# Hi-Hat2.net
KiCad netlist of a schematic drawn in EAGLE
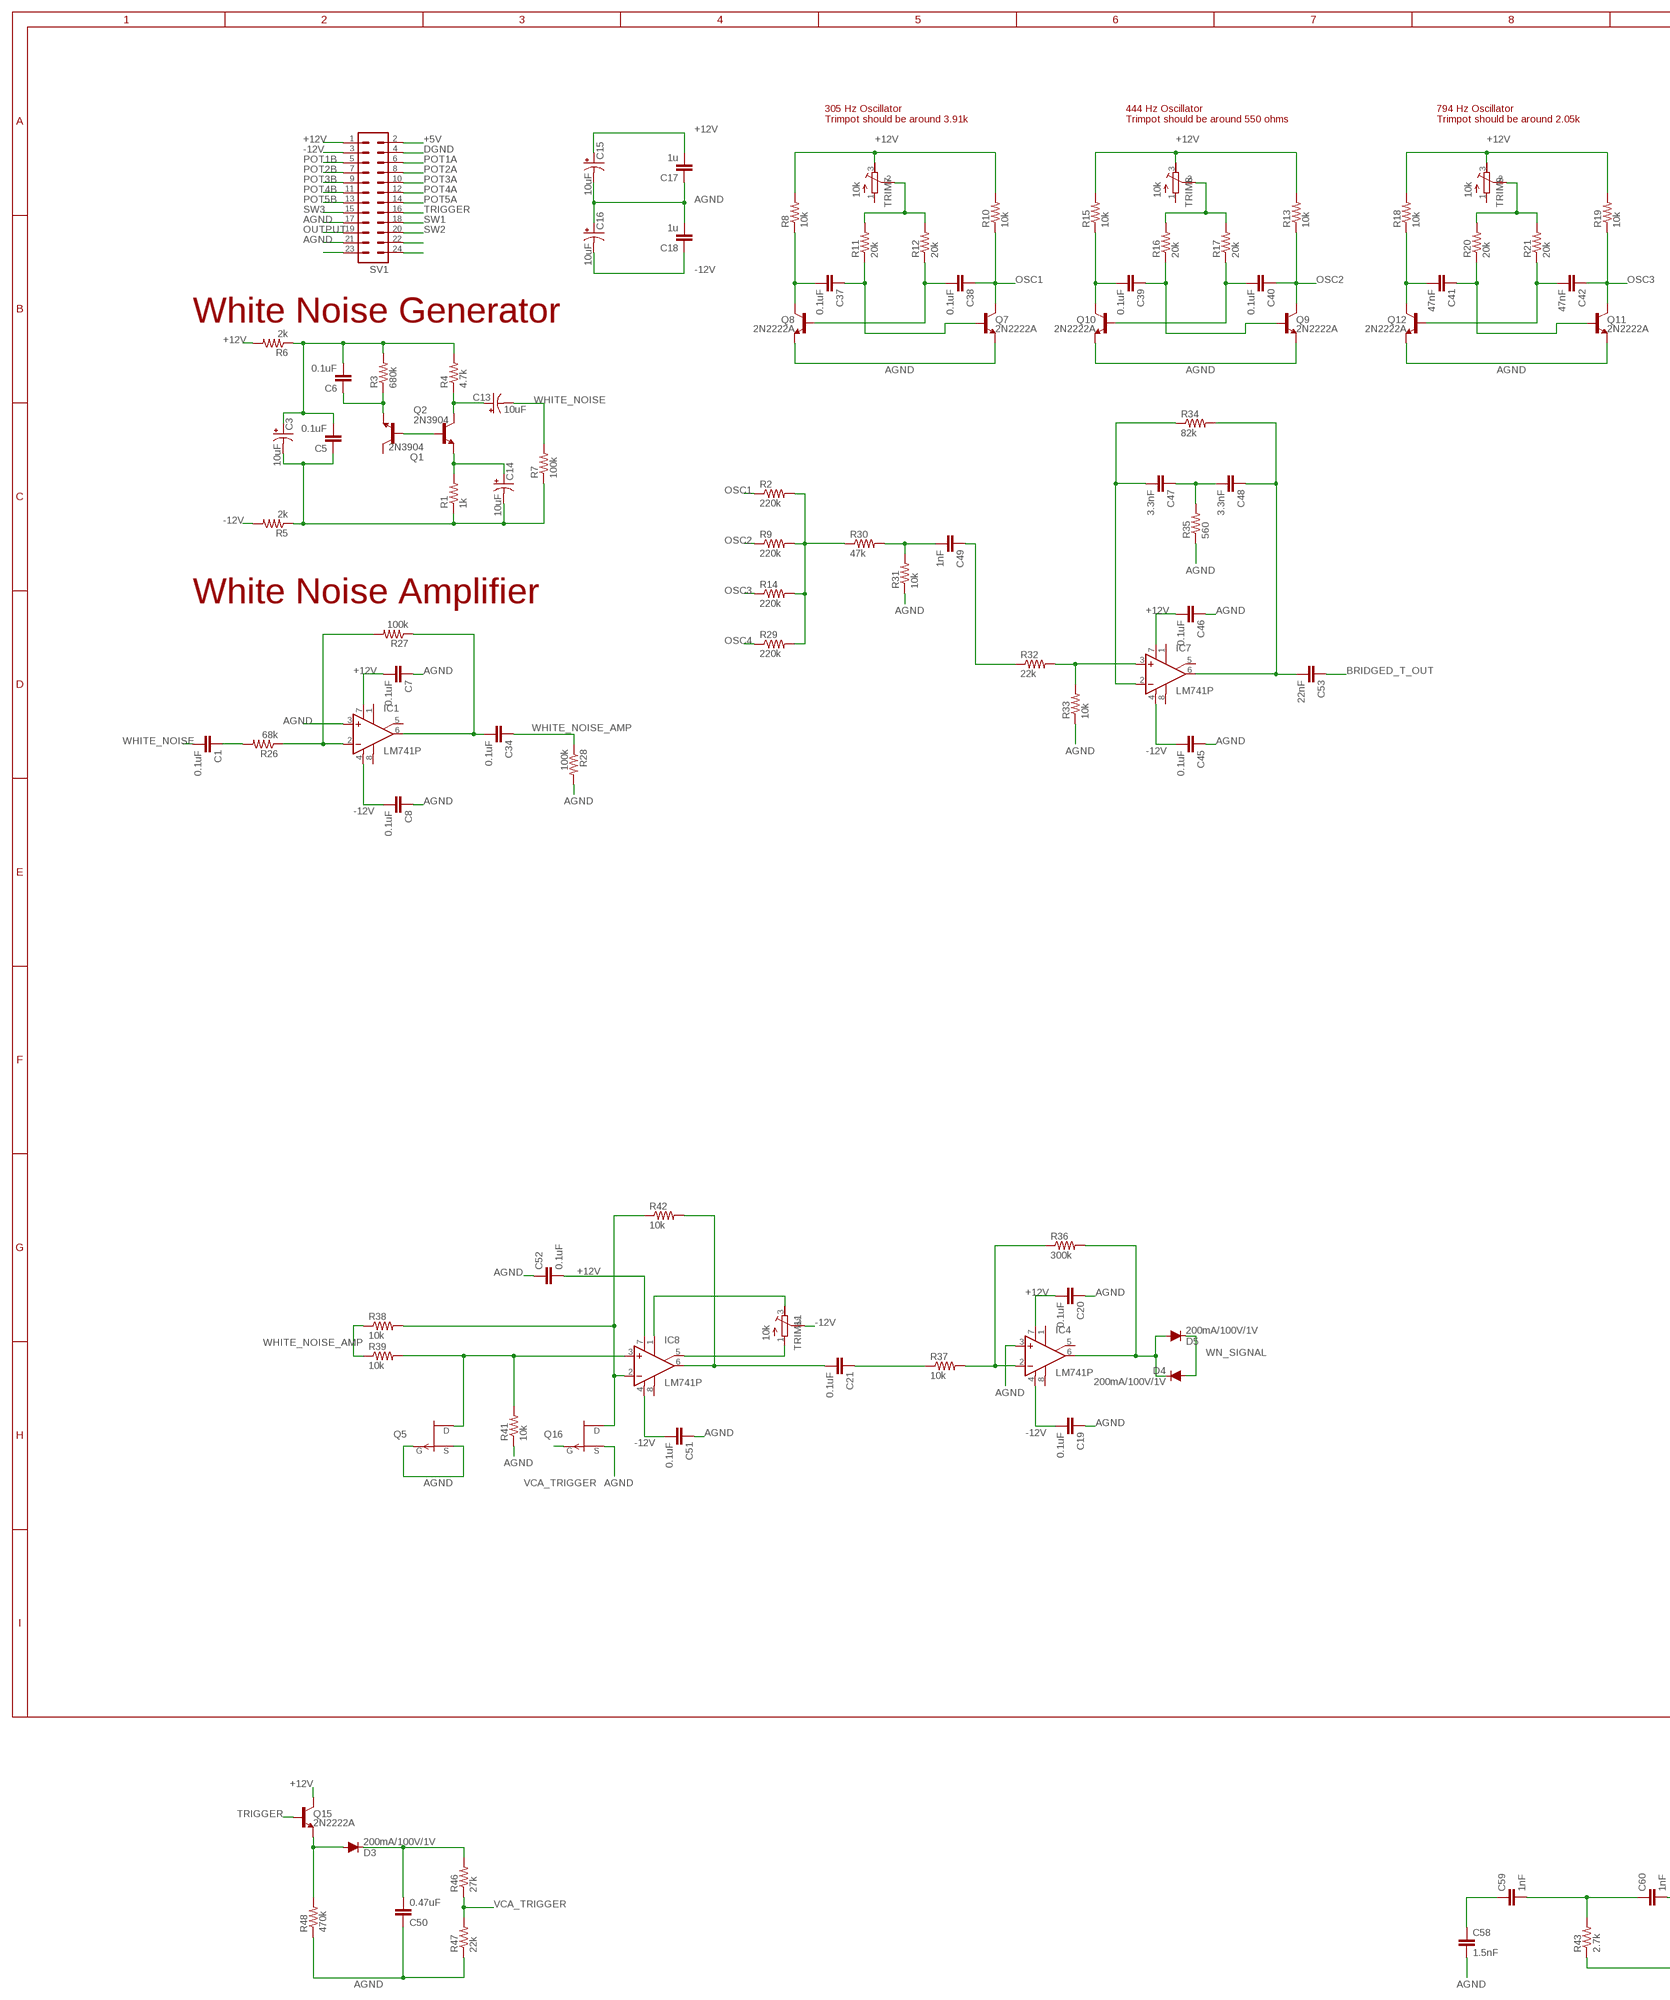
[diagram p0: schematic, sheet 1, part 1 of 2]
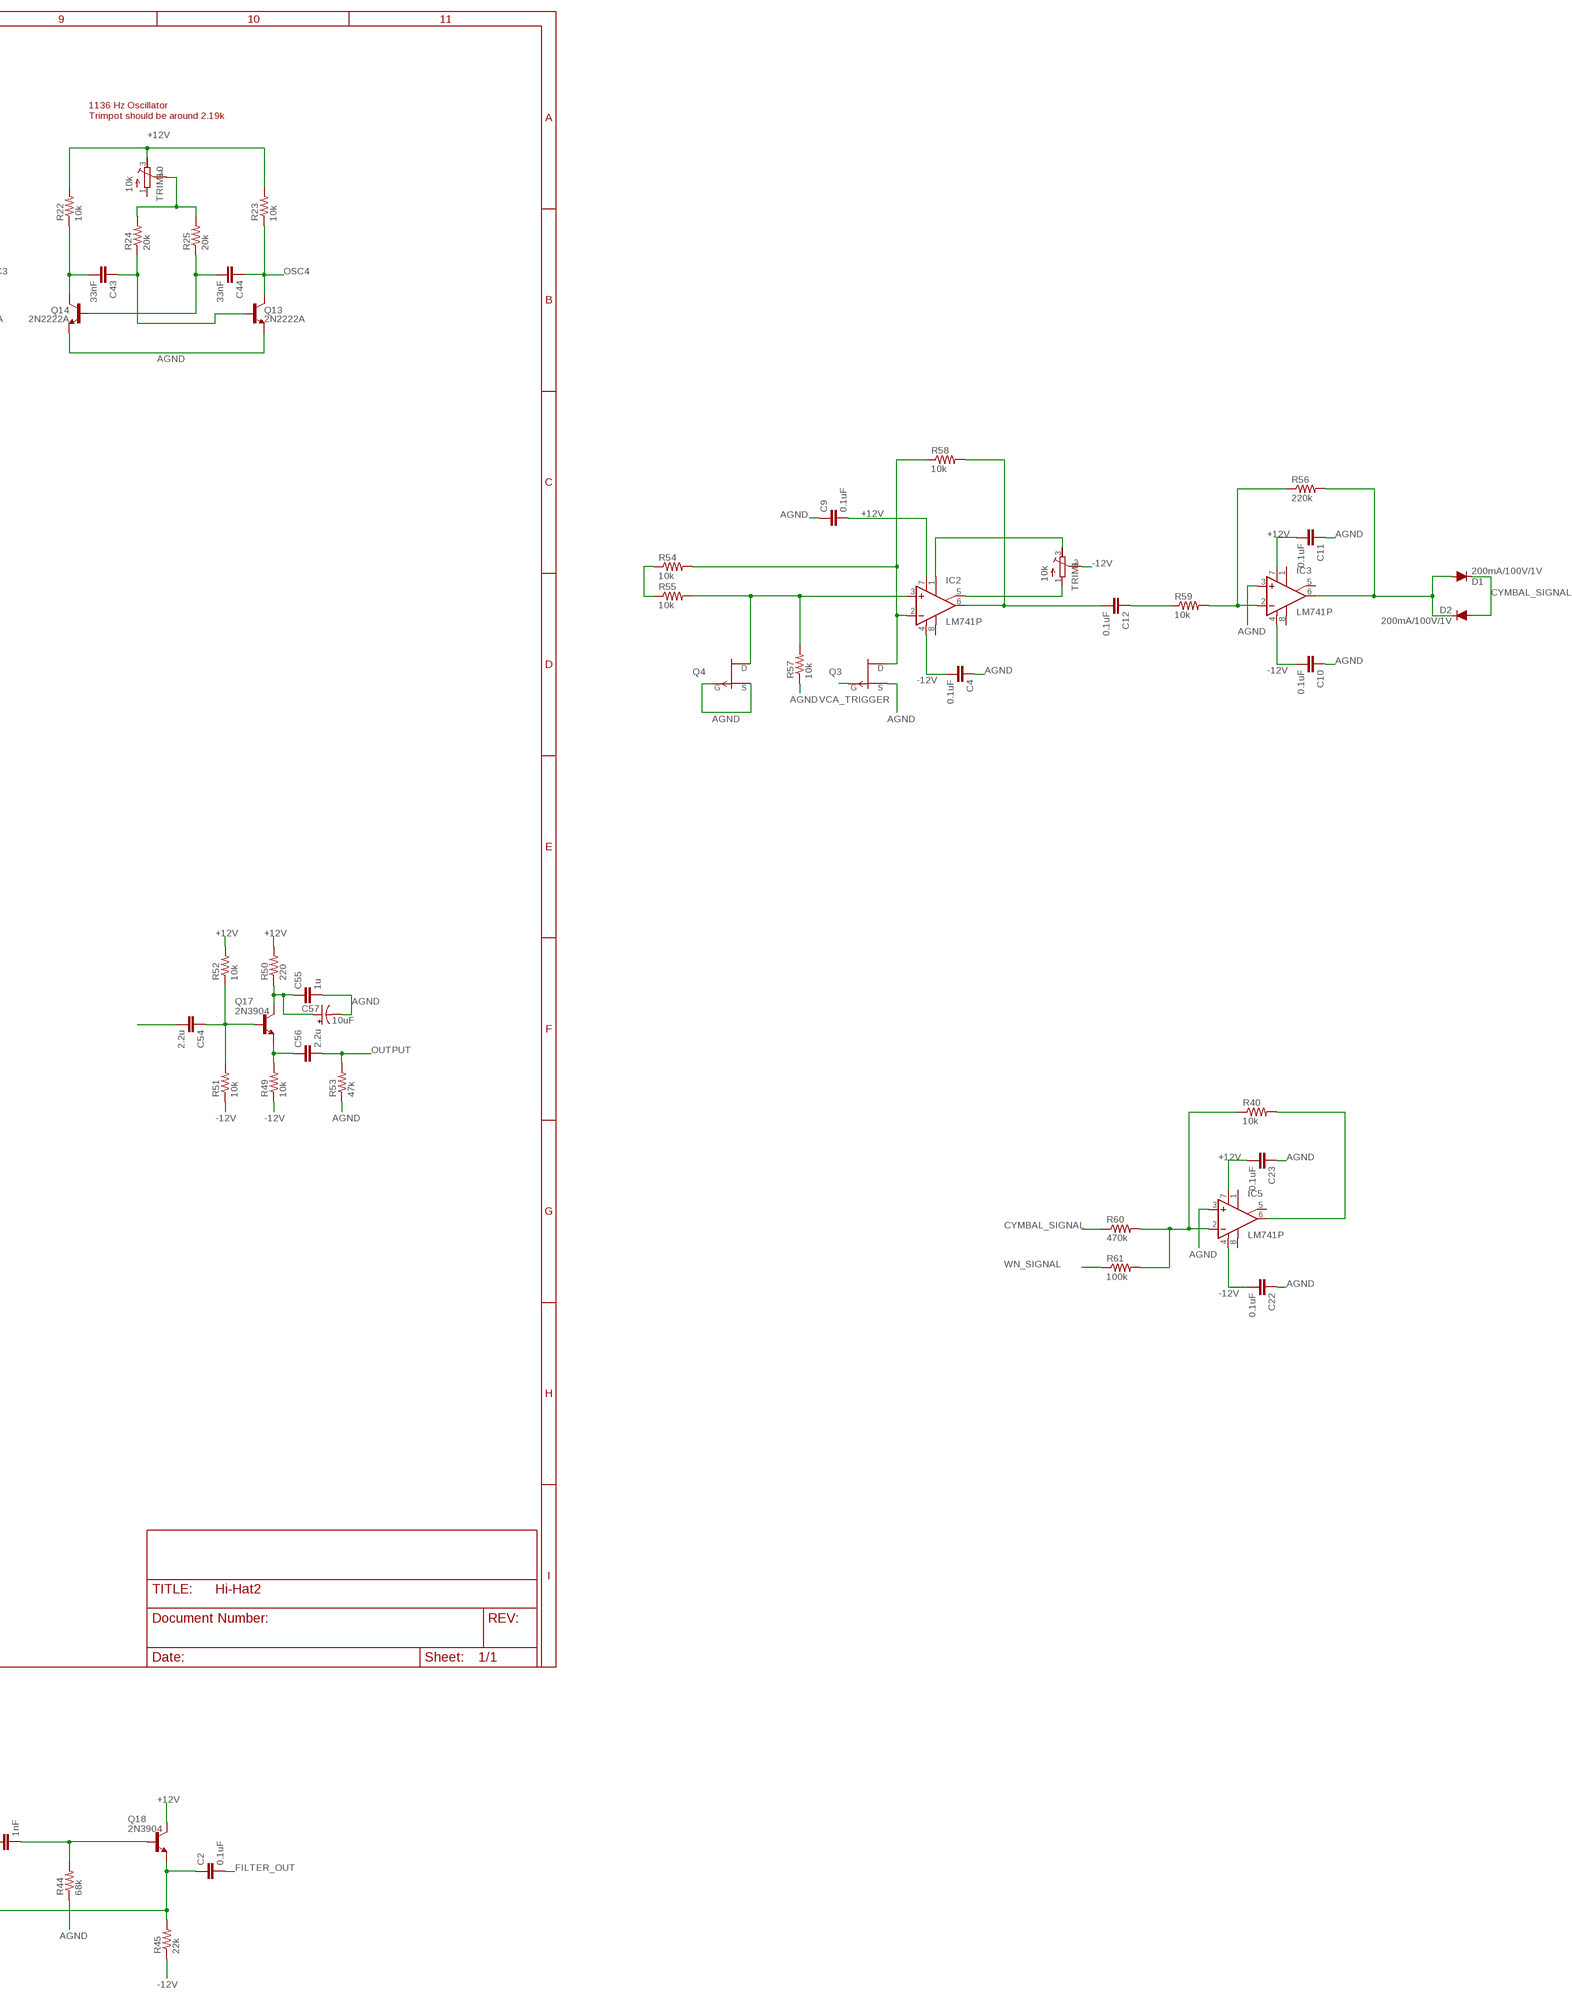
[diagram p1: schematic, sheet 1, part 2 of 2]

(export (version "E")
  (design (tool "Eeschema 10.0.6"))
  (components
    (comp (ref "C1")
      (value "0.1uF")
      (footprint "eagle-import:C050-024X044")
      (libsource (lib "eagle-import") (part "C-EU050-024X044"))
    )
    (comp (ref "C2")
      (value "0.1uF")
      (footprint "eagle-import:C050-024X044")
      (libsource (lib "eagle-import") (part "C-EU050-024X044"))
    )
    (comp (ref "C3")
      (value "10uF")
      (footprint "eagle-import:E2,5-6")
      (libsource (lib "eagle-import") (part "CPOL-USE2.5-6"))
    )
    (comp (ref "C4")
      (value "0.1uF")
      (footprint "eagle-import:C050-024X044")
      (libsource (lib "eagle-import") (part "C-EU050-024X044"))
    )
    (comp (ref "C5")
      (value "0.1uF")
      (footprint "eagle-import:C050-024X044")
      (libsource (lib "eagle-import") (part "C-EU050-024X044"))
    )
    (comp (ref "C6")
      (value "0.1uF")
      (footprint "eagle-import:C050-024X044")
      (libsource (lib "eagle-import") (part "C-EU050-024X044"))
    )
    (comp (ref "C7")
      (value "0.1uF")
      (footprint "eagle-import:C050-024X044")
      (libsource (lib "eagle-import") (part "C-EU050-024X044"))
    )
    (comp (ref "C8")
      (value "0.1uF")
      (footprint "eagle-import:C050-024X044")
      (libsource (lib "eagle-import") (part "C-EU050-024X044"))
    )
    (comp (ref "C9")
      (value "0.1uF")
      (footprint "eagle-import:C050-024X044")
      (libsource (lib "eagle-import") (part "C-EU050-024X044"))
    )
    (comp (ref "C10")
      (value "0.1uF")
      (footprint "eagle-import:C050-024X044")
      (libsource (lib "eagle-import") (part "C-EU050-024X044"))
    )
    (comp (ref "C11")
      (value "0.1uF")
      (footprint "eagle-import:C050-024X044")
      (libsource (lib "eagle-import") (part "C-EU050-024X044"))
    )
    (comp (ref "C12")
      (value "0.1uF")
      (footprint "eagle-import:C050-024X044")
      (libsource (lib "eagle-import") (part "C-EU050-024X044"))
    )
    (comp (ref "C13")
      (value "10uF")
      (footprint "eagle-import:E2,5-6")
      (libsource (lib "eagle-import") (part "CPOL-USE2.5-6"))
    )
    (comp (ref "C14")
      (value "10uF")
      (footprint "eagle-import:E2,5-6")
      (libsource (lib "eagle-import") (part "CPOL-USE2.5-6"))
    )
    (comp (ref "C15")
      (value "10uF")
      (footprint "eagle-import:E2,5-6")
      (libsource (lib "eagle-import") (part "CPOL-USE2.5-6"))
    )
    (comp (ref "C16")
      (value "10uF")
      (footprint "eagle-import:E2,5-6")
      (libsource (lib "eagle-import") (part "CPOL-USE2.5-6"))
    )
    (comp (ref "C17")
      (value "1u")
      (footprint "eagle-import:C050-024X044")
      (libsource (lib "eagle-import") (part "C-EU050-024X044"))
    )
    (comp (ref "C18")
      (value "1u")
      (footprint "eagle-import:C050-024X044")
      (libsource (lib "eagle-import") (part "C-EU050-024X044"))
    )
    (comp (ref "C19")
      (value "0.1uF")
      (footprint "eagle-import:C050-024X044")
      (libsource (lib "eagle-import") (part "C-EU050-024X044"))
    )
    (comp (ref "C20")
      (value "0.1uF")
      (footprint "eagle-import:C050-024X044")
      (libsource (lib "eagle-import") (part "C-EU050-024X044"))
    )
    (comp (ref "C21")
      (value "0.1uF")
      (footprint "eagle-import:C050-024X044")
      (libsource (lib "eagle-import") (part "C-EU050-024X044"))
    )
    (comp (ref "C22")
      (value "0.1uF")
      (footprint "eagle-import:C050-024X044")
      (libsource (lib "eagle-import") (part "C-EU050-024X044"))
    )
    (comp (ref "C23")
      (value "0.1uF")
      (footprint "eagle-import:C050-024X044")
      (libsource (lib "eagle-import") (part "C-EU050-024X044"))
    )
    (comp (ref "C34")
      (value "0.1uF")
      (footprint "eagle-import:C050-024X044")
      (libsource (lib "eagle-import") (part "C-EU050-024X044"))
    )
    (comp (ref "C37")
      (value "0.1uF")
      (footprint "eagle-import:C050-024X044")
      (libsource (lib "eagle-import") (part "C-EU050-024X044"))
    )
    (comp (ref "C38")
      (value "0.1uF")
      (footprint "eagle-import:C050-024X044")
      (libsource (lib "eagle-import") (part "C-EU050-024X044"))
    )
    (comp (ref "C39")
      (value "0.1uF")
      (footprint "eagle-import:C050-024X044")
      (libsource (lib "eagle-import") (part "C-EU050-024X044"))
    )
    (comp (ref "C40")
      (value "0.1uF")
      (footprint "eagle-import:C050-024X044")
      (libsource (lib "eagle-import") (part "C-EU050-024X044"))
    )
    (comp (ref "C41")
      (value "47nF")
      (footprint "eagle-import:C050-024X044")
      (libsource (lib "eagle-import") (part "C-EU050-024X044"))
    )
    (comp (ref "C42")
      (value "47nF")
      (footprint "eagle-import:C050-024X044")
      (libsource (lib "eagle-import") (part "C-EU050-024X044"))
    )
    (comp (ref "C43")
      (value "33nF")
      (footprint "eagle-import:C050-024X044")
      (libsource (lib "eagle-import") (part "C-EU050-024X044"))
    )
    (comp (ref "C44")
      (value "33nF")
      (footprint "eagle-import:C050-024X044")
      (libsource (lib "eagle-import") (part "C-EU050-024X044"))
    )
    (comp (ref "C45")
      (value "0.1uF")
      (footprint "eagle-import:C050-024X044")
      (libsource (lib "eagle-import") (part "C-EU050-024X044"))
    )
    (comp (ref "C46")
      (value "0.1uF")
      (footprint "eagle-import:C050-024X044")
      (libsource (lib "eagle-import") (part "C-EU050-024X044"))
    )
    (comp (ref "C47")
      (value "3.3nF")
      (footprint "eagle-import:C050-024X044")
      (libsource (lib "eagle-import") (part "C-EU050-024X044"))
    )
    (comp (ref "C48")
      (value "3.3nF")
      (footprint "eagle-import:C050-024X044")
      (libsource (lib "eagle-import") (part "C-EU050-024X044"))
    )
    (comp (ref "C49")
      (value "1nF")
      (footprint "eagle-import:C050-024X044")
      (libsource (lib "eagle-import") (part "C-EU050-024X044"))
    )
    (comp (ref "C50")
      (value "0.47uF")
      (footprint "eagle-import:C050-024X044")
      (libsource (lib "eagle-import") (part "C-EU050-024X044"))
    )
    (comp (ref "C51")
      (value "0.1uF")
      (footprint "eagle-import:C050-024X044")
      (libsource (lib "eagle-import") (part "C-EU050-024X044"))
    )
    (comp (ref "C52")
      (value "0.1uF")
      (footprint "eagle-import:C050-024X044")
      (libsource (lib "eagle-import") (part "C-EU050-024X044"))
    )
    (comp (ref "C53")
      (value "22nF")
      (footprint "eagle-import:C050-024X044")
      (libsource (lib "eagle-import") (part "C-EU050-024X044"))
    )
    (comp (ref "C54")
      (value "2.2u")
      (footprint "eagle-import:C050-024X044")
      (libsource (lib "eagle-import") (part "C-EU050-024X044"))
    )
    (comp (ref "C55")
      (value "1u")
      (footprint "eagle-import:C050-024X044")
      (libsource (lib "eagle-import") (part "C-EU050-024X044"))
    )
    (comp (ref "C56")
      (value "2.2u")
      (footprint "eagle-import:C050-024X044")
      (libsource (lib "eagle-import") (part "C-EU050-024X044"))
    )
    (comp (ref "C57")
      (value "10uF")
      (footprint "eagle-import:E2,5-6")
      (libsource (lib "eagle-import") (part "CPOL-USE2.5-6"))
    )
    (comp (ref "C58")
      (value "1.5nF")
      (footprint "eagle-import:C050-024X044")
      (libsource (lib "eagle-import") (part "C-EU050-024X044"))
    )
    (comp (ref "C59")
      (value "1nF")
      (footprint "eagle-import:C050-024X044")
      (libsource (lib "eagle-import") (part "C-EU050-024X044"))
    )
    (comp (ref "C60")
      (value "1nF")
      (footprint "eagle-import:C050-024X044")
      (libsource (lib "eagle-import") (part "C-EU050-024X044"))
    )
    (comp (ref "D1")
      (value "200mA/100V/1V")
      (footprint "eagle-import:DIODE-1N4148")
      (libsource (lib "eagle-import") (part "DIODE-1N4148"))
    )
    (comp (ref "D2")
      (value "200mA/100V/1V")
      (footprint "eagle-import:DIODE-1N4148")
      (libsource (lib "eagle-import") (part "DIODE-1N4148"))
    )
    (comp (ref "D3")
      (value "200mA/100V/1V")
      (footprint "eagle-import:DIODE-1N4148")
      (libsource (lib "eagle-import") (part "DIODE-1N4148"))
    )
    (comp (ref "D4")
      (value "200mA/100V/1V")
      (footprint "eagle-import:DIODE-1N4148")
      (libsource (lib "eagle-import") (part "DIODE-1N4148"))
    )
    (comp (ref "D5")
      (value "200mA/100V/1V")
      (footprint "eagle-import:DIODE-1N4148")
      (libsource (lib "eagle-import") (part "DIODE-1N4148"))
    )
    (comp (ref "IC1")
      (value "LM741P")
      (footprint "eagle-import:DIL08")
      (libsource (lib "eagle-import") (part "741PLM"))
    )
    (comp (ref "IC2")
      (value "LM741P")
      (footprint "eagle-import:DIL08")
      (libsource (lib "eagle-import") (part "741PLM"))
    )
    (comp (ref "IC3")
      (value "LM741P")
      (footprint "eagle-import:DIL08")
      (libsource (lib "eagle-import") (part "741PLM"))
    )
    (comp (ref "IC4")
      (value "LM741P")
      (footprint "eagle-import:DIL08")
      (libsource (lib "eagle-import") (part "741PLM"))
    )
    (comp (ref "IC5")
      (value "LM741P")
      (footprint "eagle-import:DIL08")
      (libsource (lib "eagle-import") (part "741PLM"))
    )
    (comp (ref "IC7")
      (value "LM741P")
      (footprint "eagle-import:DIL08")
      (libsource (lib "eagle-import") (part "741PLM"))
    )
    (comp (ref "IC8")
      (value "LM741P")
      (footprint "eagle-import:DIL08")
      (libsource (lib "eagle-import") (part "741PLM"))
    )
    (comp (ref "Q1")
      (value "2N3904")
      (footprint "eagle-import:TO92")
      (libsource (lib "eagle-import") (part "2N3904"))
    )
    (comp (ref "Q2")
      (value "2N3904")
      (footprint "eagle-import:TO92")
      (libsource (lib "eagle-import") (part "2N3904"))
    )
    (comp (ref "Q3")
      (value "J176")
      (footprint "eagle-import:TO-92")
      (libsource (lib "eagle-import") (part "J176"))
    )
    (comp (ref "Q4")
      (value "J176")
      (footprint "eagle-import:TO-92")
      (libsource (lib "eagle-import") (part "J176"))
    )
    (comp (ref "Q5")
      (value "J176")
      (footprint "eagle-import:TO-92")
      (libsource (lib "eagle-import") (part "J176"))
    )
    (comp (ref "Q7")
      (value "2N2222A")
      (footprint "eagle-import:TO-92")
      (libsource (lib "eagle-import") (part "TRANS_NPN-P2N2222A"))
    )
    (comp (ref "Q8")
      (value "2N2222A")
      (footprint "eagle-import:TO-92")
      (libsource (lib "eagle-import") (part "TRANS_NPN-P2N2222A"))
    )
    (comp (ref "Q9")
      (value "2N2222A")
      (footprint "eagle-import:TO-92")
      (libsource (lib "eagle-import") (part "TRANS_NPN-P2N2222A"))
    )
    (comp (ref "Q10")
      (value "2N2222A")
      (footprint "eagle-import:TO-92")
      (libsource (lib "eagle-import") (part "TRANS_NPN-P2N2222A"))
    )
    (comp (ref "Q11")
      (value "2N2222A")
      (footprint "eagle-import:TO-92")
      (libsource (lib "eagle-import") (part "TRANS_NPN-P2N2222A"))
    )
    (comp (ref "Q12")
      (value "2N2222A")
      (footprint "eagle-import:TO-92")
      (libsource (lib "eagle-import") (part "TRANS_NPN-P2N2222A"))
    )
    (comp (ref "Q13")
      (value "2N2222A")
      (footprint "eagle-import:TO-92")
      (libsource (lib "eagle-import") (part "TRANS_NPN-P2N2222A"))
    )
    (comp (ref "Q14")
      (value "2N2222A")
      (footprint "eagle-import:TO-92")
      (libsource (lib "eagle-import") (part "TRANS_NPN-P2N2222A"))
    )
    (comp (ref "Q15")
      (value "2N2222A")
      (footprint "eagle-import:TO-92")
      (libsource (lib "eagle-import") (part "TRANS_NPN-P2N2222A"))
    )
    (comp (ref "Q16")
      (value "J176")
      (footprint "eagle-import:TO-92")
      (libsource (lib "eagle-import") (part "J176"))
    )
    (comp (ref "Q17")
      (value "2N3904")
      (footprint "eagle-import:TO92")
      (libsource (lib "eagle-import") (part "2N3904"))
    )
    (comp (ref "Q18")
      (value "2N3904")
      (footprint "eagle-import:TO92")
      (libsource (lib "eagle-import") (part "2N3904"))
    )
    (comp (ref "R1")
      (value "1k")
      (footprint "eagle-import:0207_7")
      (libsource (lib "eagle-import") (part "R-US_0207/7"))
    )
    (comp (ref "R2")
      (value "220k")
      (footprint "eagle-import:0207_7")
      (libsource (lib "eagle-import") (part "R-US_0207/7"))
    )
    (comp (ref "R3")
      (value "680k")
      (footprint "eagle-import:0207_7")
      (libsource (lib "eagle-import") (part "R-US_0207/7"))
    )
    (comp (ref "R4")
      (value "4.7k")
      (footprint "eagle-import:0207_7")
      (libsource (lib "eagle-import") (part "R-US_0207/7"))
    )
    (comp (ref "R5")
      (value "2k")
      (footprint "eagle-import:0207_7")
      (libsource (lib "eagle-import") (part "R-US_0207/7"))
    )
    (comp (ref "R6")
      (value "2k")
      (footprint "eagle-import:0207_7")
      (libsource (lib "eagle-import") (part "R-US_0207/7"))
    )
    (comp (ref "R7")
      (value "100k")
      (footprint "eagle-import:0207_7")
      (libsource (lib "eagle-import") (part "R-US_0207/7"))
    )
    (comp (ref "R8")
      (value "10k")
      (footprint "eagle-import:0207_7")
      (libsource (lib "eagle-import") (part "R-US_0207/7"))
    )
    (comp (ref "R9")
      (value "220k")
      (footprint "eagle-import:0207_7")
      (libsource (lib "eagle-import") (part "R-US_0207/7"))
    )
    (comp (ref "R10")
      (value "10k")
      (footprint "eagle-import:0207_7")
      (libsource (lib "eagle-import") (part "R-US_0207/7"))
    )
    (comp (ref "R11")
      (value "20k")
      (footprint "eagle-import:0207_7")
      (libsource (lib "eagle-import") (part "R-US_0207/7"))
    )
    (comp (ref "R12")
      (value "20k")
      (footprint "eagle-import:0207_7")
      (libsource (lib "eagle-import") (part "R-US_0207/7"))
    )
    (comp (ref "R13")
      (value "10k")
      (footprint "eagle-import:0207_7")
      (libsource (lib "eagle-import") (part "R-US_0207/7"))
    )
    (comp (ref "R14")
      (value "220k")
      (footprint "eagle-import:0207_7")
      (libsource (lib "eagle-import") (part "R-US_0207/7"))
    )
    (comp (ref "R15")
      (value "10k")
      (footprint "eagle-import:0207_7")
      (libsource (lib "eagle-import") (part "R-US_0207/7"))
    )
    (comp (ref "R16")
      (value "20k")
      (footprint "eagle-import:0207_7")
      (libsource (lib "eagle-import") (part "R-US_0207/7"))
    )
    (comp (ref "R17")
      (value "20k")
      (footprint "eagle-import:0207_7")
      (libsource (lib "eagle-import") (part "R-US_0207/7"))
    )
    (comp (ref "R18")
      (value "10k")
      (footprint "eagle-import:0207_7")
      (libsource (lib "eagle-import") (part "R-US_0207/7"))
    )
    (comp (ref "R19")
      (value "10k")
      (footprint "eagle-import:0207_7")
      (libsource (lib "eagle-import") (part "R-US_0207/7"))
    )
    (comp (ref "R20")
      (value "20k")
      (footprint "eagle-import:0207_7")
      (libsource (lib "eagle-import") (part "R-US_0207/7"))
    )
    (comp (ref "R21")
      (value "20k")
      (footprint "eagle-import:0207_7")
      (libsource (lib "eagle-import") (part "R-US_0207/7"))
    )
    (comp (ref "R22")
      (value "10k")
      (footprint "eagle-import:0207_7")
      (libsource (lib "eagle-import") (part "R-US_0207/7"))
    )
    (comp (ref "R23")
      (value "10k")
      (footprint "eagle-import:0207_7")
      (libsource (lib "eagle-import") (part "R-US_0207/7"))
    )
    (comp (ref "R24")
      (value "20k")
      (footprint "eagle-import:0207_7")
      (libsource (lib "eagle-import") (part "R-US_0207/7"))
    )
    (comp (ref "R25")
      (value "20k")
      (footprint "eagle-import:0207_7")
      (libsource (lib "eagle-import") (part "R-US_0207/7"))
    )
    (comp (ref "R26")
      (value "68k")
      (footprint "eagle-import:0207_7")
      (libsource (lib "eagle-import") (part "R-US_0207/7"))
    )
    (comp (ref "R27")
      (value "100k")
      (footprint "eagle-import:0207_7")
      (libsource (lib "eagle-import") (part "R-US_0207/7"))
    )
    (comp (ref "R28")
      (value "100k")
      (footprint "eagle-import:0207_7")
      (libsource (lib "eagle-import") (part "R-US_0207/7"))
    )
    (comp (ref "R29")
      (value "220k")
      (footprint "eagle-import:0207_7")
      (libsource (lib "eagle-import") (part "R-US_0207/7"))
    )
    (comp (ref "R30")
      (value "47k")
      (footprint "eagle-import:0207_7")
      (libsource (lib "eagle-import") (part "R-US_0207/7"))
    )
    (comp (ref "R31")
      (value "10k")
      (footprint "eagle-import:0207_7")
      (libsource (lib "eagle-import") (part "R-US_0207/7"))
    )
    (comp (ref "R32")
      (value "22k")
      (footprint "eagle-import:0207_7")
      (libsource (lib "eagle-import") (part "R-US_0207/7"))
    )
    (comp (ref "R33")
      (value "10k")
      (footprint "eagle-import:0207_7")
      (libsource (lib "eagle-import") (part "R-US_0207/7"))
    )
    (comp (ref "R34")
      (value "82k")
      (footprint "eagle-import:0207_7")
      (libsource (lib "eagle-import") (part "R-US_0207/7"))
    )
    (comp (ref "R35")
      (value "560")
      (footprint "eagle-import:0207_7")
      (libsource (lib "eagle-import") (part "R-US_0207/7"))
    )
    (comp (ref "R36")
      (value "300k")
      (footprint "eagle-import:0207_7")
      (libsource (lib "eagle-import") (part "R-US_0207/7"))
    )
    (comp (ref "R37")
      (value "10k")
      (footprint "eagle-import:0207_7")
      (libsource (lib "eagle-import") (part "R-US_0207/7"))
    )
    (comp (ref "R38")
      (value "10k")
      (footprint "eagle-import:0207_7")
      (libsource (lib "eagle-import") (part "R-US_0207/7"))
    )
    (comp (ref "R39")
      (value "10k")
      (footprint "eagle-import:0207_7")
      (libsource (lib "eagle-import") (part "R-US_0207/7"))
    )
    (comp (ref "R40")
      (value "10k")
      (footprint "eagle-import:0207_7")
      (libsource (lib "eagle-import") (part "R-US_0207/7"))
    )
    (comp (ref "R41")
      (value "10k")
      (footprint "eagle-import:0207_7")
      (libsource (lib "eagle-import") (part "R-US_0207/7"))
    )
    (comp (ref "R42")
      (value "10k")
      (footprint "eagle-import:0207_7")
      (libsource (lib "eagle-import") (part "R-US_0207/7"))
    )
    (comp (ref "R43")
      (value "2.7k")
      (footprint "eagle-import:0207_7")
      (libsource (lib "eagle-import") (part "R-US_0207/7"))
    )
    (comp (ref "R44")
      (value "68k")
      (footprint "eagle-import:0207_7")
      (libsource (lib "eagle-import") (part "R-US_0207/7"))
    )
    (comp (ref "R45")
      (value "22k")
      (footprint "eagle-import:0207_7")
      (libsource (lib "eagle-import") (part "R-US_0207/7"))
    )
    (comp (ref "R46")
      (value "27k")
      (footprint "eagle-import:0207_7")
      (libsource (lib "eagle-import") (part "R-US_0207/7"))
    )
    (comp (ref "R47")
      (value "22k")
      (footprint "eagle-import:0207_7")
      (libsource (lib "eagle-import") (part "R-US_0207/7"))
    )
    (comp (ref "R48")
      (value "470k")
      (footprint "eagle-import:0207_7")
      (libsource (lib "eagle-import") (part "R-US_0207/7"))
    )
    (comp (ref "R49")
      (value "10k")
      (footprint "eagle-import:0207_7")
      (libsource (lib "eagle-import") (part "R-US_0207/7"))
    )
    (comp (ref "R50")
      (value "220")
      (footprint "eagle-import:0207_7")
      (libsource (lib "eagle-import") (part "R-US_0207/7"))
    )
    (comp (ref "R51")
      (value "10k")
      (footprint "eagle-import:0207_7")
      (libsource (lib "eagle-import") (part "R-US_0207/7"))
    )
    (comp (ref "R52")
      (value "10k")
      (footprint "eagle-import:0207_7")
      (libsource (lib "eagle-import") (part "R-US_0207/7"))
    )
    (comp (ref "R53")
      (value "47k")
      (footprint "eagle-import:0207_7")
      (libsource (lib "eagle-import") (part "R-US_0207/7"))
    )
    (comp (ref "R54")
      (value "10k")
      (footprint "eagle-import:0207_7")
      (libsource (lib "eagle-import") (part "R-US_0207/7"))
    )
    (comp (ref "R55")
      (value "10k")
      (footprint "eagle-import:0207_7")
      (libsource (lib "eagle-import") (part "R-US_0207/7"))
    )
    (comp (ref "R56")
      (value "220k")
      (footprint "eagle-import:0207_7")
      (libsource (lib "eagle-import") (part "R-US_0207/7"))
    )
    (comp (ref "R57")
      (value "10k")
      (footprint "eagle-import:0207_7")
      (libsource (lib "eagle-import") (part "R-US_0207/7"))
    )
    (comp (ref "R58")
      (value "10k")
      (footprint "eagle-import:0207_7")
      (libsource (lib "eagle-import") (part "R-US_0207/7"))
    )
    (comp (ref "R59")
      (value "10k")
      (footprint "eagle-import:0207_7")
      (libsource (lib "eagle-import") (part "R-US_0207/7"))
    )
    (comp (ref "R60")
      (value "470k")
      (footprint "eagle-import:0207_7")
      (libsource (lib "eagle-import") (part "R-US_0207/7"))
    )
    (comp (ref "R61")
      (value "100k")
      (footprint "eagle-import:0207_7")
      (libsource (lib "eagle-import") (part "R-US_0207/7"))
    )
    (comp (ref "SV1")
      (value "MA12-2")
      (footprint "eagle-import:MA12-2")
      (libsource (lib "eagle-import") (part "MA12-2"))
    )
    (comp (ref "TRIM1")
      (value "10k")
      (footprint "eagle-import:RTRIM64W")
      (libsource (lib "eagle-import") (part "R-TRIMM64W"))
    )
    (comp (ref "TRIM7")
      (value "10k")
      (footprint "eagle-import:RTRIM64W")
      (libsource (lib "eagle-import") (part "R-TRIMM64W"))
    )
    (comp (ref "TRIM8")
      (value "10k")
      (footprint "eagle-import:RTRIM64W")
      (libsource (lib "eagle-import") (part "R-TRIMM64W"))
    )
    (comp (ref "TRIM9")
      (value "10k")
      (footprint "eagle-import:RTRIM64W")
      (libsource (lib "eagle-import") (part "R-TRIMM64W"))
    )
    (comp (ref "TRIM10")
      (value "10k")
      (footprint "eagle-import:RTRIM64W")
      (libsource (lib "eagle-import") (part "R-TRIMM64W"))
    )
    (comp (ref "TRIM11")
      (value "10k")
      (footprint "eagle-import:RTRIM64W")
      (libsource (lib "eagle-import") (part "R-TRIMM64W"))
    )
  )
  (nets
    (net (code "1") (name "/+5V") (class "Default")
      (node (ref "SV1") (pin "2") (pinfunction "2_2") (pintype "passive"))
    )
    (net (code "2") (name "/+12V") (class "Default")
      (node (ref "C11") (pin "2") (pinfunction "2_2") (pintype "passive"))
      (node (ref "C15") (pin "+") (pinfunction "+_+") (pintype "passive"))
      (node (ref "C17") (pin "2") (pinfunction "2_2") (pintype "passive"))
      (node (ref "C20") (pin "2") (pinfunction "2_2") (pintype "passive"))
      (node (ref "C23") (pin "2") (pinfunction "2_2") (pintype "passive"))
      (node (ref "C46") (pin "2") (pinfunction "2_2") (pintype "passive"))
      (node (ref "C52") (pin "2") (pinfunction "2_2") (pintype "passive"))
      (node (ref "C7") (pin "2") (pinfunction "2_2") (pintype "passive"))
      (node (ref "C9") (pin "2") (pinfunction "2_2") (pintype "passive"))
      (node (ref "IC1") (pin "7") (pinfunction "V+_7") (pintype "power_in"))
      (node (ref "IC2") (pin "7") (pinfunction "V+_7") (pintype "power_in"))
      (node (ref "IC3") (pin "7") (pinfunction "V+_7") (pintype "power_in"))
      (node (ref "IC4") (pin "7") (pinfunction "V+_7") (pintype "power_in"))
      (node (ref "IC5") (pin "7") (pinfunction "V+_7") (pintype "power_in"))
      (node (ref "IC7") (pin "7") (pinfunction "V+_7") (pintype "power_in"))
      (node (ref "IC8") (pin "7") (pinfunction "V+_7") (pintype "power_in"))
      (node (ref "Q15") (pin "1") (pinfunction "C_1") (pintype "passive"))
      (node (ref "Q18") (pin "1") (pinfunction "C_1") (pintype "passive"))
      (node (ref "R10") (pin "2") (pinfunction "2_2") (pintype "passive"))
      (node (ref "R13") (pin "2") (pinfunction "2_2") (pintype "passive"))
      (node (ref "R15") (pin "2") (pinfunction "2_2") (pintype "passive"))
      (node (ref "R18") (pin "2") (pinfunction "2_2") (pintype "passive"))
      (node (ref "R19") (pin "2") (pinfunction "2_2") (pintype "passive"))
      (node (ref "R22") (pin "2") (pinfunction "2_2") (pintype "passive"))
      (node (ref "R23") (pin "2") (pinfunction "2_2") (pintype "passive"))
      (node (ref "R50") (pin "2") (pinfunction "2_2") (pintype "passive"))
      (node (ref "R52") (pin "2") (pinfunction "2_2") (pintype "passive"))
      (node (ref "R6") (pin "2") (pinfunction "2_2") (pintype "passive"))
      (node (ref "R8") (pin "2") (pinfunction "2_2") (pintype "passive"))
      (node (ref "SV1") (pin "1") (pinfunction "1_1") (pintype "passive"))
      (node (ref "TRIM10") (pin "3") (pinfunction "E_3") (pintype "passive"))
      (node (ref "TRIM7") (pin "3") (pinfunction "E_3") (pintype "passive"))
      (node (ref "TRIM8") (pin "3") (pinfunction "E_3") (pintype "passive"))
      (node (ref "TRIM9") (pin "3") (pinfunction "E_3") (pintype "passive"))
    )
    (net (code "3") (name "/-12V") (class "Default")
      (node (ref "C10") (pin "2") (pinfunction "2_2") (pintype "passive"))
      (node (ref "C16") (pin "-") (pinfunction "-_-") (pintype "passive"))
      (node (ref "C18") (pin "1") (pinfunction "1_1") (pintype "passive"))
      (node (ref "C19") (pin "2") (pinfunction "2_2") (pintype "passive"))
      (node (ref "C22") (pin "2") (pinfunction "2_2") (pintype "passive"))
      (node (ref "C4") (pin "2") (pinfunction "2_2") (pintype "passive"))
      (node (ref "C45") (pin "2") (pinfunction "2_2") (pintype "passive"))
      (node (ref "C51") (pin "2") (pinfunction "2_2") (pintype "passive"))
      (node (ref "C8") (pin "2") (pinfunction "2_2") (pintype "passive"))
      (node (ref "IC1") (pin "4") (pinfunction "V-_4") (pintype "power_in"))
      (node (ref "IC2") (pin "4") (pinfunction "V-_4") (pintype "power_in"))
      (node (ref "IC3") (pin "4") (pinfunction "V-_4") (pintype "power_in"))
      (node (ref "IC4") (pin "4") (pinfunction "V-_4") (pintype "power_in"))
      (node (ref "IC5") (pin "4") (pinfunction "V-_4") (pintype "power_in"))
      (node (ref "IC7") (pin "4") (pinfunction "V-_4") (pintype "power_in"))
      (node (ref "IC8") (pin "4") (pinfunction "V-_4") (pintype "power_in"))
      (node (ref "R45") (pin "1") (pinfunction "1_1") (pintype "passive"))
      (node (ref "R49") (pin "1") (pinfunction "1_1") (pintype "passive"))
      (node (ref "R5") (pin "2") (pinfunction "2_2") (pintype "passive"))
      (node (ref "R51") (pin "1") (pinfunction "1_1") (pintype "passive"))
      (node (ref "SV1") (pin "3") (pinfunction "3_3") (pintype "passive"))
      (node (ref "TRIM1") (pin "2") (pinfunction "S_2") (pintype "passive"))
      (node (ref "TRIM11") (pin "2") (pinfunction "S_2") (pintype "passive"))
    )
    (net (code "4") (name "/AGND") (class "Default")
      (node (ref "C10") (pin "1") (pinfunction "1_1") (pintype "passive"))
      (node (ref "C11") (pin "1") (pinfunction "1_1") (pintype "passive"))
      (node (ref "C15") (pin "-") (pinfunction "-_-") (pintype "passive"))
      (node (ref "C16") (pin "+") (pinfunction "+_+") (pintype "passive"))
      (node (ref "C17") (pin "1") (pinfunction "1_1") (pintype "passive"))
      (node (ref "C18") (pin "2") (pinfunction "2_2") (pintype "passive"))
      (node (ref "C19") (pin "1") (pinfunction "1_1") (pintype "passive"))
      (node (ref "C20") (pin "1") (pinfunction "1_1") (pintype "passive"))
      (node (ref "C22") (pin "1") (pinfunction "1_1") (pintype "passive"))
      (node (ref "C23") (pin "1") (pinfunction "1_1") (pintype "passive"))
      (node (ref "C4") (pin "1") (pinfunction "1_1") (pintype "passive"))
      (node (ref "C45") (pin "1") (pinfunction "1_1") (pintype "passive"))
      (node (ref "C46") (pin "1") (pinfunction "1_1") (pintype "passive"))
      (node (ref "C50") (pin "1") (pinfunction "1_1") (pintype "passive"))
      (node (ref "C51") (pin "1") (pinfunction "1_1") (pintype "passive"))
      (node (ref "C52") (pin "1") (pinfunction "1_1") (pintype "passive"))
      (node (ref "C55") (pin "2") (pinfunction "2_2") (pintype "passive"))
      (node (ref "C57") (pin "-") (pinfunction "-_-") (pintype "passive"))
      (node (ref "C58") (pin "2") (pinfunction "2_2") (pintype "passive"))
      (node (ref "C7") (pin "1") (pinfunction "1_1") (pintype "passive"))
      (node (ref "C8") (pin "1") (pinfunction "1_1") (pintype "passive"))
      (node (ref "C9") (pin "1") (pinfunction "1_1") (pintype "passive"))
      (node (ref "IC1") (pin "3") (pinfunction "+IN_3") (pintype "input"))
      (node (ref "IC3") (pin "3") (pinfunction "+IN_3") (pintype "input"))
      (node (ref "IC4") (pin "3") (pinfunction "+IN_3") (pintype "input"))
      (node (ref "IC5") (pin "3") (pinfunction "+IN_3") (pintype "input"))
      (node (ref "Q10") (pin "3") (pinfunction "E_3") (pintype "passive"))
      (node (ref "Q11") (pin "3") (pinfunction "E_3") (pintype "passive"))
      (node (ref "Q12") (pin "3") (pinfunction "E_3") (pintype "passive"))
      (node (ref "Q13") (pin "3") (pinfunction "E_3") (pintype "passive"))
      (node (ref "Q14") (pin "3") (pinfunction "E_3") (pintype "passive"))
      (node (ref "Q16") (pin "3") (pinfunction "S_3") (pintype "passive"))
      (node (ref "Q3") (pin "3") (pinfunction "S_3") (pintype "passive"))
      (node (ref "Q4") (pin "2") (pinfunction "G_2") (pintype "passive"))
      (node (ref "Q4") (pin "3") (pinfunction "S_3") (pintype "passive"))
      (node (ref "Q5") (pin "2") (pinfunction "G_2") (pintype "passive"))
      (node (ref "Q5") (pin "3") (pinfunction "S_3") (pintype "passive"))
      (node (ref "Q7") (pin "3") (pinfunction "E_3") (pintype "passive"))
      (node (ref "Q8") (pin "3") (pinfunction "E_3") (pintype "passive"))
      (node (ref "Q9") (pin "3") (pinfunction "E_3") (pintype "passive"))
      (node (ref "R28") (pin "2") (pinfunction "2_2") (pintype "passive"))
      (node (ref "R31") (pin "1") (pinfunction "1_1") (pintype "passive"))
      (node (ref "R33") (pin "1") (pinfunction "1_1") (pintype "passive"))
      (node (ref "R35") (pin "1") (pinfunction "1_1") (pintype "passive"))
      (node (ref "R41") (pin "1") (pinfunction "1_1") (pintype "passive"))
      (node (ref "R44") (pin "1") (pinfunction "1_1") (pintype "passive"))
      (node (ref "R47") (pin "1") (pinfunction "1_1") (pintype "passive"))
      (node (ref "R48") (pin "1") (pinfunction "1_1") (pintype "passive"))
      (node (ref "R53") (pin "1") (pinfunction "1_1") (pintype "passive"))
      (node (ref "R57") (pin "1") (pinfunction "1_1") (pintype "passive"))
      (node (ref "SV1") (pin "17") (pinfunction "17_17") (pintype "passive"))
      (node (ref "SV1") (pin "21") (pinfunction "21_21") (pintype "passive"))
    )
    (net (code "5") (name "/BRIDGED_T_OUT") (class "Default")
      (node (ref "C53") (pin "1") (pinfunction "1_1") (pintype "passive"))
    )
    (net (code "6") (name "/CYMBAL_SIGNAL") (class "Default")
      (node (ref "D1") (pin "C") (pinfunction "C_C") (pintype "passive"))
      (node (ref "D2") (pin "A") (pinfunction "A_A") (pintype "passive"))
      (node (ref "R60") (pin "1") (pinfunction "1_1") (pintype "passive"))
    )
    (net (code "7") (name "/DGND") (class "Default")
      (node (ref "SV1") (pin "4") (pinfunction "4_4") (pintype "passive"))
    )
    (net (code "8") (name "/FILTER_OUT") (class "Default")
      (node (ref "C2") (pin "2") (pinfunction "2_2") (pintype "passive"))
    )
    (net (code "9") (name "/OSC1") (class "Default")
      (node (ref "C38") (pin "1") (pinfunction "1_1") (pintype "passive"))
      (node (ref "Q7") (pin "1") (pinfunction "C_1") (pintype "passive"))
      (node (ref "R10") (pin "1") (pinfunction "1_1") (pintype "passive"))
      (node (ref "R2") (pin "1") (pinfunction "1_1") (pintype "passive"))
    )
    (net (code "10") (name "/OSC2") (class "Default")
      (node (ref "C40") (pin "1") (pinfunction "1_1") (pintype "passive"))
      (node (ref "Q9") (pin "1") (pinfunction "C_1") (pintype "passive"))
      (node (ref "R13") (pin "1") (pinfunction "1_1") (pintype "passive"))
      (node (ref "R9") (pin "1") (pinfunction "1_1") (pintype "passive"))
    )
    (net (code "11") (name "/OSC3") (class "Default")
      (node (ref "C42") (pin "1") (pinfunction "1_1") (pintype "passive"))
      (node (ref "Q11") (pin "1") (pinfunction "C_1") (pintype "passive"))
      (node (ref "R14") (pin "1") (pinfunction "1_1") (pintype "passive"))
      (node (ref "R19") (pin "1") (pinfunction "1_1") (pintype "passive"))
    )
    (net (code "12") (name "/OSC4") (class "Default")
      (node (ref "C44") (pin "1") (pinfunction "1_1") (pintype "passive"))
      (node (ref "Q13") (pin "1") (pinfunction "C_1") (pintype "passive"))
      (node (ref "R23") (pin "1") (pinfunction "1_1") (pintype "passive"))
      (node (ref "R29") (pin "1") (pinfunction "1_1") (pintype "passive"))
    )
    (net (code "13") (name "/OUTPUT") (class "Default")
      (node (ref "C56") (pin "2") (pinfunction "2_2") (pintype "passive"))
      (node (ref "R53") (pin "2") (pinfunction "2_2") (pintype "passive"))
      (node (ref "SV1") (pin "19") (pinfunction "19_19") (pintype "passive"))
    )
    (net (code "14") (name "/POT1A") (class "Default")
      (node (ref "SV1") (pin "6") (pinfunction "6_6") (pintype "passive"))
    )
    (net (code "15") (name "/POT1B") (class "Default")
      (node (ref "SV1") (pin "5") (pinfunction "5_5") (pintype "passive"))
    )
    (net (code "16") (name "/POT2A") (class "Default")
      (node (ref "SV1") (pin "8") (pinfunction "8_8") (pintype "passive"))
    )
    (net (code "17") (name "/POT2B") (class "Default")
      (node (ref "SV1") (pin "7") (pinfunction "7_7") (pintype "passive"))
    )
    (net (code "18") (name "/POT3A") (class "Default")
      (node (ref "SV1") (pin "10") (pinfunction "10_10") (pintype "passive"))
    )
    (net (code "19") (name "/POT3B") (class "Default")
      (node (ref "SV1") (pin "9") (pinfunction "9_9") (pintype "passive"))
    )
    (net (code "20") (name "/POT4A") (class "Default")
      (node (ref "SV1") (pin "12") (pinfunction "12_12") (pintype "passive"))
    )
    (net (code "21") (name "/POT4B") (class "Default")
      (node (ref "SV1") (pin "11") (pinfunction "11_11") (pintype "passive"))
    )
    (net (code "22") (name "/POT5A") (class "Default")
      (node (ref "SV1") (pin "14") (pinfunction "14_14") (pintype "passive"))
    )
    (net (code "23") (name "/POT5B") (class "Default")
      (node (ref "SV1") (pin "13") (pinfunction "13_13") (pintype "passive"))
    )
    (net (code "24") (name "/SW1") (class "Default")
      (node (ref "C58") (pin "1") (pinfunction "1_1") (pintype "passive"))
      (node (ref "C59") (pin "1") (pinfunction "1_1") (pintype "passive"))
      (node (ref "SV1") (pin "18") (pinfunction "18_18") (pintype "passive"))
    )
    (net (code "25") (name "/SW2") (class "Default")
      (node (ref "SV1") (pin "20") (pinfunction "20_20") (pintype "passive"))
    )
    (net (code "26") (name "/SW3") (class "Default")
      (node (ref "SV1") (pin "15") (pinfunction "15_15") (pintype "passive"))
    )
    (net (code "27") (name "/TRIGGER") (class "Default")
      (node (ref "Q15") (pin "2") (pinfunction "B_2") (pintype "passive"))
      (node (ref "SV1") (pin "16") (pinfunction "16_16") (pintype "passive"))
    )
    (net (code "28") (name "/VCA_TRIGGER") (class "Default")
      (node (ref "Q16") (pin "2") (pinfunction "G_2") (pintype "passive"))
      (node (ref "Q3") (pin "2") (pinfunction "G_2") (pintype "passive"))
      (node (ref "R46") (pin "1") (pinfunction "1_1") (pintype "passive"))
      (node (ref "R47") (pin "2") (pinfunction "2_2") (pintype "passive"))
    )
    (net (code "29") (name "/WHITE_NOISE") (class "Default")
      (node (ref "C1") (pin "2") (pinfunction "2_2") (pintype "passive"))
      (node (ref "C13") (pin "-") (pinfunction "-_-") (pintype "passive"))
      (node (ref "R7") (pin "2") (pinfunction "2_2") (pintype "passive"))
    )
    (net (code "30") (name "/WHITE_NOISE_AMP") (class "Default")
      (node (ref "C34") (pin "1") (pinfunction "1_1") (pintype "passive"))
      (node (ref "R28") (pin "1") (pinfunction "1_1") (pintype "passive"))
      (node (ref "R38") (pin "1") (pinfunction "1_1") (pintype "passive"))
      (node (ref "R39") (pin "1") (pinfunction "1_1") (pintype "passive"))
    )
    (net (code "31") (name "/WN_SIGNAL") (class "Default")
      (node (ref "D4") (pin "A") (pinfunction "A_A") (pintype "passive"))
      (node (ref "D5") (pin "C") (pinfunction "C_C") (pintype "passive"))
      (node (ref "R61") (pin "1") (pinfunction "1_1") (pintype "passive"))
    )
    (net (code "32") (name "Net-(C1-Pad1)") (class "Default")
      (node (ref "C1") (pin "1") (pinfunction "1_1") (pintype "passive"))
      (node (ref "R26") (pin "2") (pinfunction "2_2") (pintype "passive"))
    )
    (net (code "33") (name "Net-(C3-Pad+)") (class "Default")
      (node (ref "C3") (pin "+") (pinfunction "+_+") (pintype "passive"))
      (node (ref "C5") (pin "2") (pinfunction "2_2") (pintype "passive"))
      (node (ref "C6") (pin "2") (pinfunction "2_2") (pintype "passive"))
      (node (ref "R3") (pin "2") (pinfunction "2_2") (pintype "passive"))
      (node (ref "R4") (pin "2") (pinfunction "2_2") (pintype "passive"))
      (node (ref "R6") (pin "1") (pinfunction "1_1") (pintype "passive"))
    )
    (net (code "34") (name "Net-(C12-Pad1)") (class "Default")
      (node (ref "C12") (pin "1") (pinfunction "1_1") (pintype "passive"))
      (node (ref "R59") (pin "1") (pinfunction "1_1") (pintype "passive"))
    )
    (net (code "35") (name "Net-(C14-Pad-)") (class "Default")
      (node (ref "C14") (pin "-") (pinfunction "-_-") (pintype "passive"))
      (node (ref "C3") (pin "-") (pinfunction "-_-") (pintype "passive"))
      (node (ref "C5") (pin "1") (pinfunction "1_1") (pintype "passive"))
      (node (ref "R1") (pin "1") (pinfunction "1_1") (pintype "passive"))
      (node (ref "R5") (pin "1") (pinfunction "1_1") (pintype "passive"))
      (node (ref "R7") (pin "1") (pinfunction "1_1") (pintype "passive"))
    )
    (net (code "36") (name "Net-(C21-Pad1)") (class "Default")
      (node (ref "C21") (pin "1") (pinfunction "1_1") (pintype "passive"))
      (node (ref "R37") (pin "1") (pinfunction "1_1") (pintype "passive"))
    )
    (net (code "37") (name "Net-(C47-Pad1)") (class "Default")
      (node (ref "C47") (pin "1") (pinfunction "1_1") (pintype "passive"))
      (node (ref "C48") (pin "2") (pinfunction "2_2") (pintype "passive"))
      (node (ref "R35") (pin "2") (pinfunction "2_2") (pintype "passive"))
    )
    (net (code "38") (name "Net-(C49-Pad1)") (class "Default")
      (node (ref "C49") (pin "1") (pinfunction "1_1") (pintype "passive"))
      (node (ref "R32") (pin "1") (pinfunction "1_1") (pintype "passive"))
    )
    (net (code "39") (name "Net-(C49-Pad2)") (class "Default")
      (node (ref "C49") (pin "2") (pinfunction "2_2") (pintype "passive"))
      (node (ref "R30") (pin "2") (pinfunction "2_2") (pintype "passive"))
      (node (ref "R31") (pin "2") (pinfunction "2_2") (pintype "passive"))
    )
    (net (code "40") (name "Net-(C50-Pad2)") (class "Default")
      (node (ref "C50") (pin "2") (pinfunction "2_2") (pintype "passive"))
      (node (ref "D3") (pin "C") (pinfunction "C_C") (pintype "passive"))
      (node (ref "R46") (pin "2") (pinfunction "2_2") (pintype "passive"))
    )
    (net (code "41") (name "Net-(C59-Pad2)") (class "Default")
      (node (ref "C59") (pin "2") (pinfunction "2_2") (pintype "passive"))
      (node (ref "C60") (pin "1") (pinfunction "1_1") (pintype "passive"))
      (node (ref "R43") (pin "2") (pinfunction "2_2") (pintype "passive"))
    )
    (net (code "42") (name "Net-(IC1--IN)") (class "Default")
      (node (ref "IC1") (pin "2") (pinfunction "-IN_2") (pintype "input"))
      (node (ref "R26") (pin "1") (pinfunction "1_1") (pintype "passive"))
      (node (ref "R27") (pin "2") (pinfunction "2_2") (pintype "passive"))
    )
    (net (code "43") (name "Net-(IC1-OUT)") (class "Default")
      (node (ref "C34") (pin "2") (pinfunction "2_2") (pintype "passive"))
      (node (ref "IC1") (pin "6") (pinfunction "OUT_6") (pintype "output"))
      (node (ref "R27") (pin "1") (pinfunction "1_1") (pintype "passive"))
    )
    (net (code "44") (name "Net-(IC2-+IN)") (class "Default")
      (node (ref "IC2") (pin "3") (pinfunction "+IN_3") (pintype "input"))
      (node (ref "Q4") (pin "1") (pinfunction "D_1") (pintype "passive"))
      (node (ref "R55") (pin "2") (pinfunction "2_2") (pintype "passive"))
      (node (ref "R57") (pin "2") (pinfunction "2_2") (pintype "passive"))
    )
    (net (code "45") (name "Net-(IC2--IN)") (class "Default")
      (node (ref "IC2") (pin "2") (pinfunction "-IN_2") (pintype "input"))
      (node (ref "Q3") (pin "1") (pinfunction "D_1") (pintype "passive"))
      (node (ref "R54") (pin "2") (pinfunction "2_2") (pintype "passive"))
      (node (ref "R58") (pin "1") (pinfunction "1_1") (pintype "passive"))
    )
    (net (code "46") (name "Net-(IC2-ON1)") (class "Default")
      (node (ref "IC2") (pin "1") (pinfunction "ON1_1") (pintype "passive"))
      (node (ref "TRIM1") (pin "3") (pinfunction "E_3") (pintype "passive"))
    )
    (net (code "47") (name "Net-(IC2-ON2)") (class "Default")
      (node (ref "IC2") (pin "5") (pinfunction "ON2_5") (pintype "passive"))
      (node (ref "TRIM1") (pin "1") (pinfunction "A_1") (pintype "passive"))
    )
    (net (code "48") (name "Net-(IC2-OUT)") (class "Default")
      (node (ref "C12") (pin "2") (pinfunction "2_2") (pintype "passive"))
      (node (ref "IC2") (pin "6") (pinfunction "OUT_6") (pintype "output"))
      (node (ref "R58") (pin "2") (pinfunction "2_2") (pintype "passive"))
    )
    (net (code "49") (name "Net-(IC3--IN)") (class "Default")
      (node (ref "IC3") (pin "2") (pinfunction "-IN_2") (pintype "input"))
      (node (ref "R56") (pin "1") (pinfunction "1_1") (pintype "passive"))
      (node (ref "R59") (pin "2") (pinfunction "2_2") (pintype "passive"))
    )
    (net (code "50") (name "Net-(IC3-OUT)") (class "Default")
      (node (ref "D1") (pin "A") (pinfunction "A_A") (pintype "passive"))
      (node (ref "D2") (pin "C") (pinfunction "C_C") (pintype "passive"))
      (node (ref "IC3") (pin "6") (pinfunction "OUT_6") (pintype "output"))
      (node (ref "R56") (pin "2") (pinfunction "2_2") (pintype "passive"))
    )
    (net (code "51") (name "Net-(IC4--IN)") (class "Default")
      (node (ref "IC4") (pin "2") (pinfunction "-IN_2") (pintype "input"))
      (node (ref "R36") (pin "1") (pinfunction "1_1") (pintype "passive"))
      (node (ref "R37") (pin "2") (pinfunction "2_2") (pintype "passive"))
    )
    (net (code "52") (name "Net-(IC4-OUT)") (class "Default")
      (node (ref "D4") (pin "C") (pinfunction "C_C") (pintype "passive"))
      (node (ref "D5") (pin "A") (pinfunction "A_A") (pintype "passive"))
      (node (ref "IC4") (pin "6") (pinfunction "OUT_6") (pintype "output"))
      (node (ref "R36") (pin "2") (pinfunction "2_2") (pintype "passive"))
    )
    (net (code "53") (name "Net-(IC5--IN)") (class "Default")
      (node (ref "IC5") (pin "2") (pinfunction "-IN_2") (pintype "input"))
      (node (ref "R40") (pin "1") (pinfunction "1_1") (pintype "passive"))
      (node (ref "R60") (pin "2") (pinfunction "2_2") (pintype "passive"))
      (node (ref "R61") (pin "2") (pinfunction "2_2") (pintype "passive"))
    )
    (net (code "54") (name "Net-(IC5-OUT)") (class "Default")
      (node (ref "IC5") (pin "6") (pinfunction "OUT_6") (pintype "output"))
      (node (ref "R40") (pin "2") (pinfunction "2_2") (pintype "passive"))
    )
    (net (code "55") (name "Net-(IC7-+IN)") (class "Default")
      (node (ref "IC7") (pin "3") (pinfunction "+IN_3") (pintype "input"))
      (node (ref "R32") (pin "2") (pinfunction "2_2") (pintype "passive"))
      (node (ref "R33") (pin "2") (pinfunction "2_2") (pintype "passive"))
    )
    (net (code "56") (name "Net-(IC7--IN)") (class "Default")
      (node (ref "C47") (pin "2") (pinfunction "2_2") (pintype "passive"))
      (node (ref "IC7") (pin "2") (pinfunction "-IN_2") (pintype "input"))
      (node (ref "R34") (pin "1") (pinfunction "1_1") (pintype "passive"))
    )
    (net (code "57") (name "Net-(IC7-OUT)") (class "Default")
      (node (ref "C48") (pin "1") (pinfunction "1_1") (pintype "passive"))
      (node (ref "C53") (pin "2") (pinfunction "2_2") (pintype "passive"))
      (node (ref "IC7") (pin "6") (pinfunction "OUT_6") (pintype "output"))
      (node (ref "R34") (pin "2") (pinfunction "2_2") (pintype "passive"))
    )
    (net (code "58") (name "Net-(IC8-+IN)") (class "Default")
      (node (ref "IC8") (pin "3") (pinfunction "+IN_3") (pintype "input"))
      (node (ref "Q5") (pin "1") (pinfunction "D_1") (pintype "passive"))
      (node (ref "R39") (pin "2") (pinfunction "2_2") (pintype "passive"))
      (node (ref "R41") (pin "2") (pinfunction "2_2") (pintype "passive"))
    )
    (net (code "59") (name "Net-(IC8--IN)") (class "Default")
      (node (ref "IC8") (pin "2") (pinfunction "-IN_2") (pintype "input"))
      (node (ref "Q16") (pin "1") (pinfunction "D_1") (pintype "passive"))
      (node (ref "R38") (pin "2") (pinfunction "2_2") (pintype "passive"))
      (node (ref "R42") (pin "1") (pinfunction "1_1") (pintype "passive"))
    )
    (net (code "60") (name "Net-(IC8-ON1)") (class "Default")
      (node (ref "IC8") (pin "1") (pinfunction "ON1_1") (pintype "passive"))
      (node (ref "TRIM11") (pin "3") (pinfunction "E_3") (pintype "passive"))
    )
    (net (code "61") (name "Net-(IC8-ON2)") (class "Default")
      (node (ref "IC8") (pin "5") (pinfunction "ON2_5") (pintype "passive"))
      (node (ref "TRIM11") (pin "1") (pinfunction "A_1") (pintype "passive"))
    )
    (net (code "62") (name "Net-(IC8-OUT)") (class "Default")
      (node (ref "C21") (pin "2") (pinfunction "2_2") (pintype "passive"))
      (node (ref "IC8") (pin "6") (pinfunction "OUT_6") (pintype "output"))
      (node (ref "R42") (pin "2") (pinfunction "2_2") (pintype "passive"))
    )
    (net (code "63") (name "Net-(Q1-B)") (class "Default")
      (node (ref "Q1") (pin "2") (pinfunction "B_2") (pintype "passive"))
      (node (ref "Q2") (pin "2") (pinfunction "B_2") (pintype "passive"))
    )
    (net (code "64") (name "Net-(Q1-E)") (class "Default")
      (node (ref "C6") (pin "1") (pinfunction "1_1") (pintype "passive"))
      (node (ref "Q1") (pin "3") (pinfunction "E_3") (pintype "passive"))
      (node (ref "R3") (pin "1") (pinfunction "1_1") (pintype "passive"))
    )
    (net (code "65") (name "Net-(Q2-C)") (class "Default")
      (node (ref "C13") (pin "+") (pinfunction "+_+") (pintype "passive"))
      (node (ref "Q2") (pin "1") (pinfunction "C_1") (pintype "passive"))
      (node (ref "R4") (pin "1") (pinfunction "1_1") (pintype "passive"))
    )
    (net (code "66") (name "Net-(Q2-E)") (class "Default")
      (node (ref "C14") (pin "+") (pinfunction "+_+") (pintype "passive"))
      (node (ref "Q2") (pin "3") (pinfunction "E_3") (pintype "passive"))
      (node (ref "R1") (pin "2") (pinfunction "2_2") (pintype "passive"))
    )
    (net (code "67") (name "Net-(Q7-B)") (class "Default")
      (node (ref "C37") (pin "1") (pinfunction "1_1") (pintype "passive"))
      (node (ref "Q7") (pin "2") (pinfunction "B_2") (pintype "passive"))
      (node (ref "R11") (pin "1") (pinfunction "1_1") (pintype "passive"))
    )
    (net (code "68") (name "Net-(Q8-B)") (class "Default")
      (node (ref "C38") (pin "2") (pinfunction "2_2") (pintype "passive"))
      (node (ref "Q8") (pin "2") (pinfunction "B_2") (pintype "passive"))
      (node (ref "R12") (pin "1") (pinfunction "1_1") (pintype "passive"))
    )
    (net (code "69") (name "Net-(Q8-C)") (class "Default")
      (node (ref "C37") (pin "2") (pinfunction "2_2") (pintype "passive"))
      (node (ref "Q8") (pin "1") (pinfunction "C_1") (pintype "passive"))
      (node (ref "R8") (pin "1") (pinfunction "1_1") (pintype "passive"))
    )
    (net (code "70") (name "Net-(Q9-B)") (class "Default")
      (node (ref "C39") (pin "1") (pinfunction "1_1") (pintype "passive"))
      (node (ref "Q9") (pin "2") (pinfunction "B_2") (pintype "passive"))
      (node (ref "R16") (pin "1") (pinfunction "1_1") (pintype "passive"))
    )
    (net (code "71") (name "Net-(Q10-B)") (class "Default")
      (node (ref "C40") (pin "2") (pinfunction "2_2") (pintype "passive"))
      (node (ref "Q10") (pin "2") (pinfunction "B_2") (pintype "passive"))
      (node (ref "R17") (pin "1") (pinfunction "1_1") (pintype "passive"))
    )
    (net (code "72") (name "Net-(Q10-C)") (class "Default")
      (node (ref "C39") (pin "2") (pinfunction "2_2") (pintype "passive"))
      (node (ref "Q10") (pin "1") (pinfunction "C_1") (pintype "passive"))
      (node (ref "R15") (pin "1") (pinfunction "1_1") (pintype "passive"))
    )
    (net (code "73") (name "Net-(Q11-B)") (class "Default")
      (node (ref "C41") (pin "1") (pinfunction "1_1") (pintype "passive"))
      (node (ref "Q11") (pin "2") (pinfunction "B_2") (pintype "passive"))
      (node (ref "R20") (pin "1") (pinfunction "1_1") (pintype "passive"))
    )
    (net (code "74") (name "Net-(Q12-B)") (class "Default")
      (node (ref "C42") (pin "2") (pinfunction "2_2") (pintype "passive"))
      (node (ref "Q12") (pin "2") (pinfunction "B_2") (pintype "passive"))
      (node (ref "R21") (pin "1") (pinfunction "1_1") (pintype "passive"))
    )
    (net (code "75") (name "Net-(Q12-C)") (class "Default")
      (node (ref "C41") (pin "2") (pinfunction "2_2") (pintype "passive"))
      (node (ref "Q12") (pin "1") (pinfunction "C_1") (pintype "passive"))
      (node (ref "R18") (pin "1") (pinfunction "1_1") (pintype "passive"))
    )
    (net (code "76") (name "Net-(Q13-B)") (class "Default")
      (node (ref "C43") (pin "1") (pinfunction "1_1") (pintype "passive"))
      (node (ref "Q13") (pin "2") (pinfunction "B_2") (pintype "passive"))
      (node (ref "R24") (pin "1") (pinfunction "1_1") (pintype "passive"))
    )
    (net (code "77") (name "Net-(Q14-B)") (class "Default")
      (node (ref "C44") (pin "2") (pinfunction "2_2") (pintype "passive"))
      (node (ref "Q14") (pin "2") (pinfunction "B_2") (pintype "passive"))
      (node (ref "R25") (pin "1") (pinfunction "1_1") (pintype "passive"))
    )
    (net (code "78") (name "Net-(Q14-C)") (class "Default")
      (node (ref "C43") (pin "2") (pinfunction "2_2") (pintype "passive"))
      (node (ref "Q14") (pin "1") (pinfunction "C_1") (pintype "passive"))
      (node (ref "R22") (pin "1") (pinfunction "1_1") (pintype "passive"))
    )
    (net (code "79") (name "Net-(Q15-E)") (class "Default")
      (node (ref "D3") (pin "A") (pinfunction "A_A") (pintype "passive"))
      (node (ref "Q15") (pin "3") (pinfunction "E_3") (pintype "passive"))
      (node (ref "R48") (pin "2") (pinfunction "2_2") (pintype "passive"))
    )
    (net (code "80") (name "Net-(Q17-B)") (class "Default")
      (node (ref "C54") (pin "1") (pinfunction "1_1") (pintype "passive"))
      (node (ref "Q17") (pin "2") (pinfunction "B_2") (pintype "passive"))
      (node (ref "R51") (pin "2") (pinfunction "2_2") (pintype "passive"))
      (node (ref "R52") (pin "1") (pinfunction "1_1") (pintype "passive"))
    )
    (net (code "81") (name "Net-(Q17-C)") (class "Default")
      (node (ref "C55") (pin "1") (pinfunction "1_1") (pintype "passive"))
      (node (ref "C57") (pin "+") (pinfunction "+_+") (pintype "passive"))
      (node (ref "Q17") (pin "1") (pinfunction "C_1") (pintype "passive"))
      (node (ref "R50") (pin "1") (pinfunction "1_1") (pintype "passive"))
    )
    (net (code "82") (name "Net-(Q17-E)") (class "Default")
      (node (ref "C56") (pin "1") (pinfunction "1_1") (pintype "passive"))
      (node (ref "Q17") (pin "3") (pinfunction "E_3") (pintype "passive"))
      (node (ref "R49") (pin "2") (pinfunction "2_2") (pintype "passive"))
    )
    (net (code "83") (name "Net-(Q18-B)") (class "Default")
      (node (ref "C60") (pin "2") (pinfunction "2_2") (pintype "passive"))
      (node (ref "Q18") (pin "2") (pinfunction "B_2") (pintype "passive"))
      (node (ref "R44") (pin "2") (pinfunction "2_2") (pintype "passive"))
    )
    (net (code "84") (name "Net-(Q18-E)") (class "Default")
      (node (ref "C2") (pin "1") (pinfunction "1_1") (pintype "passive"))
      (node (ref "Q18") (pin "3") (pinfunction "E_3") (pintype "passive"))
      (node (ref "R43") (pin "1") (pinfunction "1_1") (pintype "passive"))
      (node (ref "R45") (pin "2") (pinfunction "2_2") (pintype "passive"))
    )
    (net (code "85") (name "Net-(R14-Pad2)") (class "Default")
      (node (ref "R14") (pin "2") (pinfunction "2_2") (pintype "passive"))
      (node (ref "R2") (pin "2") (pinfunction "2_2") (pintype "passive"))
      (node (ref "R29") (pin "2") (pinfunction "2_2") (pintype "passive"))
      (node (ref "R30") (pin "1") (pinfunction "1_1") (pintype "passive"))
      (node (ref "R9") (pin "2") (pinfunction "2_2") (pintype "passive"))
    )
    (net (code "86") (name "Net-(R54-Pad1)") (class "Default")
      (node (ref "R54") (pin "1") (pinfunction "1_1") (pintype "passive"))
      (node (ref "R55") (pin "1") (pinfunction "1_1") (pintype "passive"))
    )
    (net (code "87") (name "Net-(TRIM7-S)") (class "Default")
      (node (ref "R11") (pin "2") (pinfunction "2_2") (pintype "passive"))
      (node (ref "R12") (pin "2") (pinfunction "2_2") (pintype "passive"))
      (node (ref "TRIM7") (pin "2") (pinfunction "S_2") (pintype "passive"))
    )
    (net (code "88") (name "Net-(TRIM8-S)") (class "Default")
      (node (ref "R16") (pin "2") (pinfunction "2_2") (pintype "passive"))
      (node (ref "R17") (pin "2") (pinfunction "2_2") (pintype "passive"))
      (node (ref "TRIM8") (pin "2") (pinfunction "S_2") (pintype "passive"))
    )
    (net (code "89") (name "Net-(TRIM9-S)") (class "Default")
      (node (ref "R20") (pin "2") (pinfunction "2_2") (pintype "passive"))
      (node (ref "R21") (pin "2") (pinfunction "2_2") (pintype "passive"))
      (node (ref "TRIM9") (pin "2") (pinfunction "S_2") (pintype "passive"))
    )
    (net (code "90") (name "Net-(TRIM10-S)") (class "Default")
      (node (ref "R24") (pin "2") (pinfunction "2_2") (pintype "passive"))
      (node (ref "R25") (pin "2") (pinfunction "2_2") (pintype "passive"))
      (node (ref "TRIM10") (pin "2") (pinfunction "S_2") (pintype "passive"))
    )
    (net (code "91") (name "unconnected-(C54-Pad2)") (class "Default")
      (node (ref "C54") (pin "2") (pinfunction "2_2") (pintype "passive"))
    )
    (net (code "92") (name "unconnected-(IC1-ON1-Pad1)") (class "Default")
      (node (ref "IC1") (pin "1") (pinfunction "ON1_1") (pintype "passive"))
    )
    (net (code "93") (name "unconnected-(IC1-ON2-Pad5)") (class "Default")
      (node (ref "IC1") (pin "5") (pinfunction "ON2_5") (pintype "passive"))
    )
    (net (code "94") (name "unconnected-(IC1-OPT-Pad8)") (class "Default")
      (node (ref "IC1") (pin "8") (pinfunction "OPT_8") (pintype "passive"))
    )
    (net (code "95") (name "unconnected-(IC2-OPT-Pad8)") (class "Default")
      (node (ref "IC2") (pin "8") (pinfunction "OPT_8") (pintype "passive"))
    )
    (net (code "96") (name "unconnected-(IC3-ON1-Pad1)") (class "Default")
      (node (ref "IC3") (pin "1") (pinfunction "ON1_1") (pintype "passive"))
    )
    (net (code "97") (name "unconnected-(IC3-ON2-Pad5)") (class "Default")
      (node (ref "IC3") (pin "5") (pinfunction "ON2_5") (pintype "passive"))
    )
    (net (code "98") (name "unconnected-(IC3-OPT-Pad8)") (class "Default")
      (node (ref "IC3") (pin "8") (pinfunction "OPT_8") (pintype "passive"))
    )
    (net (code "99") (name "unconnected-(IC4-ON1-Pad1)") (class "Default")
      (node (ref "IC4") (pin "1") (pinfunction "ON1_1") (pintype "passive"))
    )
    (net (code "100") (name "unconnected-(IC4-ON2-Pad5)") (class "Default")
      (node (ref "IC4") (pin "5") (pinfunction "ON2_5") (pintype "passive"))
    )
    (net (code "101") (name "unconnected-(IC4-OPT-Pad8)") (class "Default")
      (node (ref "IC4") (pin "8") (pinfunction "OPT_8") (pintype "passive"))
    )
    (net (code "102") (name "unconnected-(IC5-ON1-Pad1)") (class "Default")
      (node (ref "IC5") (pin "1") (pinfunction "ON1_1") (pintype "passive"))
    )
    (net (code "103") (name "unconnected-(IC5-ON2-Pad5)") (class "Default")
      (node (ref "IC5") (pin "5") (pinfunction "ON2_5") (pintype "passive"))
    )
    (net (code "104") (name "unconnected-(IC5-OPT-Pad8)") (class "Default")
      (node (ref "IC5") (pin "8") (pinfunction "OPT_8") (pintype "passive"))
    )
    (net (code "105") (name "unconnected-(IC7-ON1-Pad1)") (class "Default")
      (node (ref "IC7") (pin "1") (pinfunction "ON1_1") (pintype "passive"))
    )
    (net (code "106") (name "unconnected-(IC7-ON2-Pad5)") (class "Default")
      (node (ref "IC7") (pin "5") (pinfunction "ON2_5") (pintype "passive"))
    )
    (net (code "107") (name "unconnected-(IC7-OPT-Pad8)") (class "Default")
      (node (ref "IC7") (pin "8") (pinfunction "OPT_8") (pintype "passive"))
    )
    (net (code "108") (name "unconnected-(IC8-OPT-Pad8)") (class "Default")
      (node (ref "IC8") (pin "8") (pinfunction "OPT_8") (pintype "passive"))
    )
    (net (code "109") (name "unconnected-(Q1-C-Pad1)") (class "Default")
      (node (ref "Q1") (pin "1") (pinfunction "C_1") (pintype "passive"))
    )
    (net (code "110") (name "unconnected-(SV1-Pad22)") (class "Default")
      (node (ref "SV1") (pin "22") (pinfunction "22_22") (pintype "passive"))
    )
    (net (code "111") (name "unconnected-(SV1-Pad23)") (class "Default")
      (node (ref "SV1") (pin "23") (pinfunction "23_23") (pintype "passive"))
    )
    (net (code "112") (name "unconnected-(SV1-Pad24)") (class "Default")
      (node (ref "SV1") (pin "24") (pinfunction "24_24") (pintype "passive"))
    )
    (net (code "113") (name "unconnected-(TRIM7-A-Pad1)") (class "Default")
      (node (ref "TRIM7") (pin "1") (pinfunction "A_1") (pintype "passive"))
    )
    (net (code "114") (name "unconnected-(TRIM8-A-Pad1)") (class "Default")
      (node (ref "TRIM8") (pin "1") (pinfunction "A_1") (pintype "passive"))
    )
    (net (code "115") (name "unconnected-(TRIM9-A-Pad1)") (class "Default")
      (node (ref "TRIM9") (pin "1") (pinfunction "A_1") (pintype "passive"))
    )
    (net (code "116") (name "unconnected-(TRIM10-A-Pad1)") (class "Default")
      (node (ref "TRIM10") (pin "1") (pinfunction "A_1") (pintype "passive"))
    )
  )
)
